# MPU-9250v2.net
KiCad netlist of a schematic drawn in EAGLE
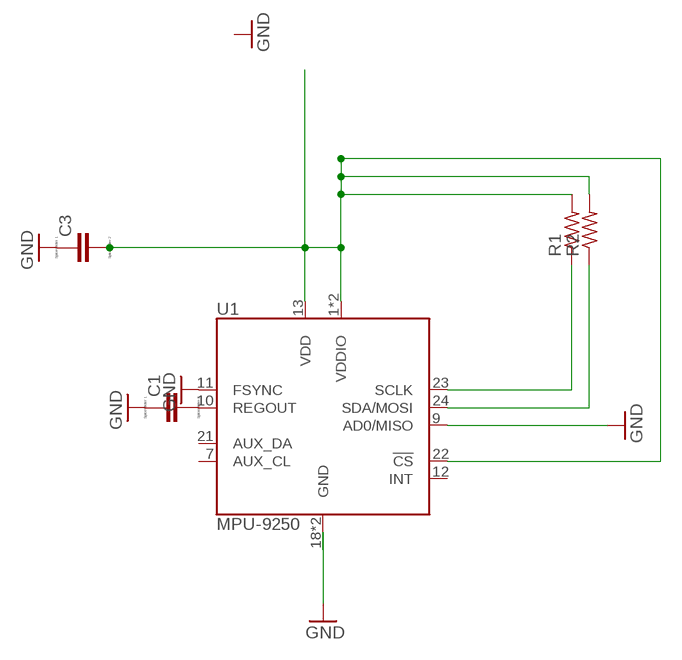
[diagram p0: schematic, sheet 1]

(export (version "E")
  (design (tool "Eeschema 10.0.6"))
  (components
    (comp (ref "C1")
      (value "CC0603")
      (footprint "eagle-import:C0603")
      (libsource (lib "eagle-import") (part "CC0603"))
    )
    (comp (ref "C3")
      (value "CC0603")
      (footprint "eagle-import:C0603")
      (libsource (lib "eagle-import") (part "CC0603"))
    )
    (comp (ref "R1")
      (value "R-US_R0603")
      (footprint "eagle-import:R0603")
      (libsource (lib "eagle-import") (part "R-US_R0603"))
    )
    (comp (ref "R2")
      (value "R-US_R0603")
      (footprint "eagle-import:R0603")
      (libsource (lib "eagle-import") (part "R-US_R0603"))
    )
    (comp (ref "U1")
      (value "MPU-9250")
      (footprint "eagle-import:QFN-24_3MM")
      (libsource (lib "eagle-import") (part "MPU-9250"))
    )
  )
  (nets
    (net (code "1") (name "GND") (class "Default")
      (node (ref "C1") (pin "1") (pinfunction "1_1") (pintype "passive"))
      (node (ref "C3") (pin "1") (pinfunction "1_1") (pintype "passive"))
      (node (ref "U1") (pin "11") (pinfunction "FSYNC_11") (pintype "bidirectional"))
      (node (ref "U1") (pin "18") (pinfunction "GND_18") (pintype "bidirectional"))
      (node (ref "U1") (pin "20") (pinfunction "GND_20") (pintype "bidirectional"))
      (node (ref "U1") (pin "9") (pinfunction "AD0/MISO_9") (pintype "bidirectional"))
    )
    (net (code "2") (name "Net-(U1-REGOUT)") (class "Default")
      (node (ref "C1") (pin "2") (pinfunction "2_2") (pintype "passive"))
      (node (ref "U1") (pin "10") (pinfunction "REGOUT_10") (pintype "bidirectional"))
    )
    (net (code "3") (name "Net-(U1-SCLK)") (class "Default")
      (node (ref "R1") (pin "1") (pinfunction "1_1") (pintype "passive"))
      (node (ref "U1") (pin "23") (pinfunction "SCLK_23") (pintype "bidirectional"))
    )
    (net (code "4") (name "Net-(U1-SDA{slash}MOSI)") (class "Default")
      (node (ref "R2") (pin "1") (pinfunction "1_1") (pintype "passive"))
      (node (ref "U1") (pin "24") (pinfunction "SDA/MOSI_24") (pintype "bidirectional"))
    )
    (net (code "5") (name "Net-(U1-VDD)") (class "Default")
      (node (ref "C3") (pin "2") (pinfunction "2_2") (pintype "passive"))
      (node (ref "R1") (pin "2") (pinfunction "2_2") (pintype "passive"))
      (node (ref "R2") (pin "2") (pinfunction "2_2") (pintype "passive"))
      (node (ref "U1") (pin "1") (pinfunction "VDDIO_1") (pintype "bidirectional"))
      (node (ref "U1") (pin "13") (pinfunction "VDD_13") (pintype "bidirectional"))
      (node (ref "U1") (pin "22") (pinfunction "~{CS}_22") (pintype "bidirectional"))
      (node (ref "U1") (pin "8") (pinfunction "VDDIO_8") (pintype "bidirectional"))
    )
    (net (code "6") (name "unconnected-(U1-AUX_CL-Pad7)") (class "Default")
      (node (ref "U1") (pin "7") (pinfunction "AUX_CL_7") (pintype "bidirectional"))
    )
    (net (code "7") (name "unconnected-(U1-AUX_DA-Pad21)") (class "Default")
      (node (ref "U1") (pin "21") (pinfunction "AUX_DA_21") (pintype "bidirectional"))
    )
    (net (code "8") (name "unconnected-(U1-INT-Pad12)") (class "Default")
      (node (ref "U1") (pin "12") (pinfunction "INT_12") (pintype "bidirectional"))
    )
  )
)
